# MadHaddr.net
KiCad netlist of a schematic drawn in EAGLE
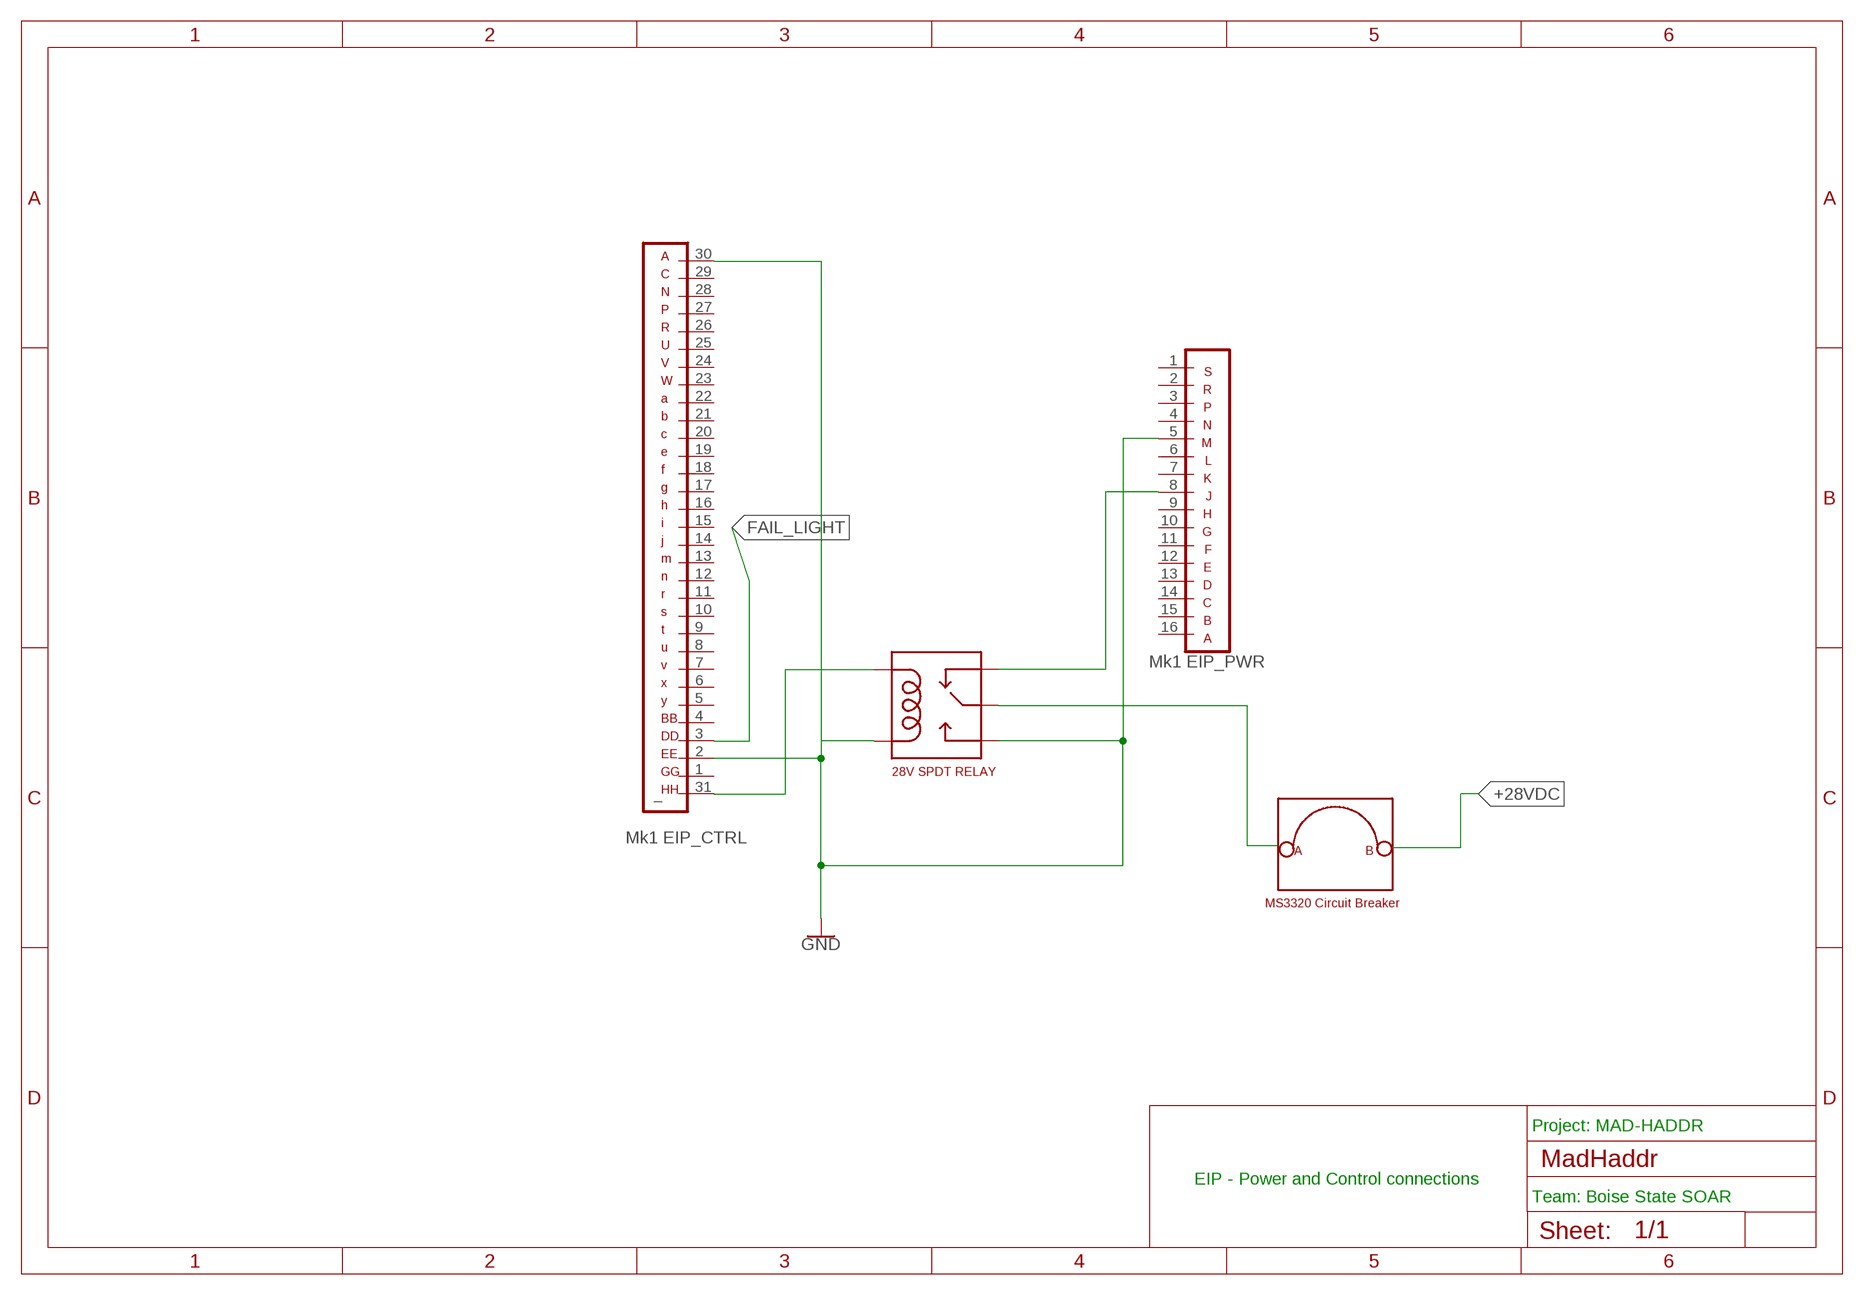
[diagram p0: schematic, sheet 1]

(export (version "E")
  (design (tool "Eeschema 10.0.6"))
  (components
    (comp (ref "J2")
      (value "SDGDSGG")
      (footprint "eagle-import:1X30")
      (libsource (lib "eagle-import") (part "SDGDSGG"))
    )
    (comp (ref "U$1")
      (value "MK1_EIP_PWR")
      (footprint "eagle-import:1X16")
      (libsource (lib "eagle-import") (part "MK1_EIP_PWR"))
    )
    (comp (ref "U$2")
      (value "BREAKER")
      (footprint "eagle-import:BREAKER")
      (libsource (lib "eagle-import") (part "BREAKER"))
    )
    (comp (ref "U$3")
      (value "SPDT_RELAY")
      (footprint "eagle-import:RELAY-JZC")
      (libsource (lib "eagle-import") (part "SPDT_RELAY"))
    )
  )
  (nets
    (net (code "1") (name "+28VDC") (class "Default")
      (node (ref "U$2") (pin "P$1") (pinfunction "P$1_P$1") (pintype "bidirectional"))
    )
    (net (code "2") (name "FAIL_LIGHT") (class "Default")
      (node (ref "J2") (pin "3") (pinfunction "3_3") (pintype "passive"))
    )
    (net (code "3") (name "GND") (class "Default")
      (node (ref "J2") (pin "2") (pinfunction "2_2") (pintype "passive"))
      (node (ref "J2") (pin "30") (pinfunction "30_30") (pintype "passive"))
      (node (ref "U$1") (pin "5") (pinfunction "5_5") (pintype "passive"))
      (node (ref "U$3") (pin "2") (pinfunction "COIL2_2") (pintype "bidirectional"))
      (node (ref "U$3") (pin "5") (pinfunction "NO_5") (pintype "bidirectional"))
    )
    (net (code "4") (name "Net-(J2-_)") (class "Default")
      (node (ref "J2") (pin "31") (pinfunction "__31") (pintype "passive"))
      (node (ref "U$3") (pin "1") (pinfunction "COIL1_1") (pintype "bidirectional"))
    )
    (net (code "5") (name "Net-(U$3-MAIN)") (class "Default")
      (node (ref "U$2") (pin "P$2") (pinfunction "P$2_P$2") (pintype "bidirectional"))
      (node (ref "U$3") (pin "3") (pinfunction "MAIN_3") (pintype "bidirectional"))
    )
    (net (code "6") (name "Net-(U$3-NC)") (class "Default")
      (node (ref "U$1") (pin "8") (pinfunction "8_8") (pintype "passive"))
      (node (ref "U$3") (pin "4") (pinfunction "NC_4") (pintype "bidirectional"))
    )
    (net (code "7") (name "unconnected-(J2-Pad1)") (class "Default")
      (node (ref "J2") (pin "1") (pinfunction "1_1") (pintype "passive"))
    )
    (net (code "8") (name "unconnected-(J2-Pad4)") (class "Default")
      (node (ref "J2") (pin "4") (pinfunction "4_4") (pintype "passive"))
    )
    (net (code "9") (name "unconnected-(J2-Pad5)") (class "Default")
      (node (ref "J2") (pin "5") (pinfunction "5_5") (pintype "passive"))
    )
    (net (code "10") (name "unconnected-(J2-Pad6)") (class "Default")
      (node (ref "J2") (pin "6") (pinfunction "6_6") (pintype "passive"))
    )
    (net (code "11") (name "unconnected-(J2-Pad7)") (class "Default")
      (node (ref "J2") (pin "7") (pinfunction "7_7") (pintype "passive"))
    )
    (net (code "12") (name "unconnected-(J2-Pad8)") (class "Default")
      (node (ref "J2") (pin "8") (pinfunction "8_8") (pintype "passive"))
    )
    (net (code "13") (name "unconnected-(J2-Pad9)") (class "Default")
      (node (ref "J2") (pin "9") (pinfunction "9_9") (pintype "passive"))
    )
    (net (code "14") (name "unconnected-(J2-Pad10)") (class "Default")
      (node (ref "J2") (pin "10") (pinfunction "10_10") (pintype "passive"))
    )
    (net (code "15") (name "unconnected-(J2-Pad11)") (class "Default")
      (node (ref "J2") (pin "11") (pinfunction "11_11") (pintype "passive"))
    )
    (net (code "16") (name "unconnected-(J2-Pad12)") (class "Default")
      (node (ref "J2") (pin "12") (pinfunction "12_12") (pintype "passive"))
    )
    (net (code "17") (name "unconnected-(J2-Pad13)") (class "Default")
      (node (ref "J2") (pin "13") (pinfunction "13_13") (pintype "passive"))
    )
    (net (code "18") (name "unconnected-(J2-Pad14)") (class "Default")
      (node (ref "J2") (pin "14") (pinfunction "14_14") (pintype "passive"))
    )
    (net (code "19") (name "unconnected-(J2-Pad15)") (class "Default")
      (node (ref "J2") (pin "15") (pinfunction "15_15") (pintype "passive"))
    )
    (net (code "20") (name "unconnected-(J2-Pad16)") (class "Default")
      (node (ref "J2") (pin "16") (pinfunction "16_16") (pintype "passive"))
    )
    (net (code "21") (name "unconnected-(J2-Pad17)") (class "Default")
      (node (ref "J2") (pin "17") (pinfunction "17_17") (pintype "passive"))
    )
    (net (code "22") (name "unconnected-(J2-Pad18)") (class "Default")
      (node (ref "J2") (pin "18") (pinfunction "18_18") (pintype "passive"))
    )
    (net (code "23") (name "unconnected-(J2-Pad19)") (class "Default")
      (node (ref "J2") (pin "19") (pinfunction "19_19") (pintype "passive"))
    )
    (net (code "24") (name "unconnected-(J2-Pad20)") (class "Default")
      (node (ref "J2") (pin "20") (pinfunction "20_20") (pintype "passive"))
    )
    (net (code "25") (name "unconnected-(J2-Pad21)") (class "Default")
      (node (ref "J2") (pin "21") (pinfunction "21_21") (pintype "passive"))
    )
    (net (code "26") (name "unconnected-(J2-Pad22)") (class "Default")
      (node (ref "J2") (pin "22") (pinfunction "22_22") (pintype "passive"))
    )
    (net (code "27") (name "unconnected-(J2-Pad23)") (class "Default")
      (node (ref "J2") (pin "23") (pinfunction "23_23") (pintype "passive"))
    )
    (net (code "28") (name "unconnected-(J2-Pad24)") (class "Default")
      (node (ref "J2") (pin "24") (pinfunction "24_24") (pintype "passive"))
    )
    (net (code "29") (name "unconnected-(J2-Pad25)") (class "Default")
      (node (ref "J2") (pin "25") (pinfunction "25_25") (pintype "passive"))
    )
    (net (code "30") (name "unconnected-(J2-Pad26)") (class "Default")
      (node (ref "J2") (pin "26") (pinfunction "26_26") (pintype "passive"))
    )
    (net (code "31") (name "unconnected-(J2-Pad27)") (class "Default")
      (node (ref "J2") (pin "27") (pinfunction "27_27") (pintype "passive"))
    )
    (net (code "32") (name "unconnected-(J2-Pad28)") (class "Default")
      (node (ref "J2") (pin "28") (pinfunction "28_28") (pintype "passive"))
    )
    (net (code "33") (name "unconnected-(J2-Pad29)") (class "Default")
      (node (ref "J2") (pin "29") (pinfunction "29_29") (pintype "passive"))
    )
    (net (code "34") (name "unconnected-(U$1-Pad1)") (class "Default")
      (node (ref "U$1") (pin "1") (pinfunction "1_1") (pintype "passive"))
    )
    (net (code "35") (name "unconnected-(U$1-Pad2)") (class "Default")
      (node (ref "U$1") (pin "2") (pinfunction "2_2") (pintype "passive"))
    )
    (net (code "36") (name "unconnected-(U$1-Pad3)") (class "Default")
      (node (ref "U$1") (pin "3") (pinfunction "3_3") (pintype "passive"))
    )
    (net (code "37") (name "unconnected-(U$1-Pad4)") (class "Default")
      (node (ref "U$1") (pin "4") (pinfunction "4_4") (pintype "passive"))
    )
    (net (code "38") (name "unconnected-(U$1-Pad6)") (class "Default")
      (node (ref "U$1") (pin "6") (pinfunction "6_6") (pintype "passive"))
    )
    (net (code "39") (name "unconnected-(U$1-Pad7)") (class "Default")
      (node (ref "U$1") (pin "7") (pinfunction "7_7") (pintype "passive"))
    )
    (net (code "40") (name "unconnected-(U$1-Pad9)") (class "Default")
      (node (ref "U$1") (pin "9") (pinfunction "9_9") (pintype "passive"))
    )
    (net (code "41") (name "unconnected-(U$1-Pad10)") (class "Default")
      (node (ref "U$1") (pin "10") (pinfunction "10_10") (pintype "passive"))
    )
    (net (code "42") (name "unconnected-(U$1-Pad11)") (class "Default")
      (node (ref "U$1") (pin "11") (pinfunction "11_11") (pintype "passive"))
    )
    (net (code "43") (name "unconnected-(U$1-Pad12)") (class "Default")
      (node (ref "U$1") (pin "12") (pinfunction "12_12") (pintype "passive"))
    )
    (net (code "44") (name "unconnected-(U$1-Pad13)") (class "Default")
      (node (ref "U$1") (pin "13") (pinfunction "13_13") (pintype "passive"))
    )
    (net (code "45") (name "unconnected-(U$1-Pad14)") (class "Default")
      (node (ref "U$1") (pin "14") (pinfunction "14_14") (pintype "passive"))
    )
    (net (code "46") (name "unconnected-(U$1-Pad15)") (class "Default")
      (node (ref "U$1") (pin "15") (pinfunction "15_15") (pintype "passive"))
    )
    (net (code "47") (name "unconnected-(U$1-Pad16)") (class "Default")
      (node (ref "U$1") (pin "16") (pinfunction "16_16") (pintype "passive"))
    )
  )
)
